# 18_Type_C.net
KiCad netlist of a schematic drawn in Altium Designer
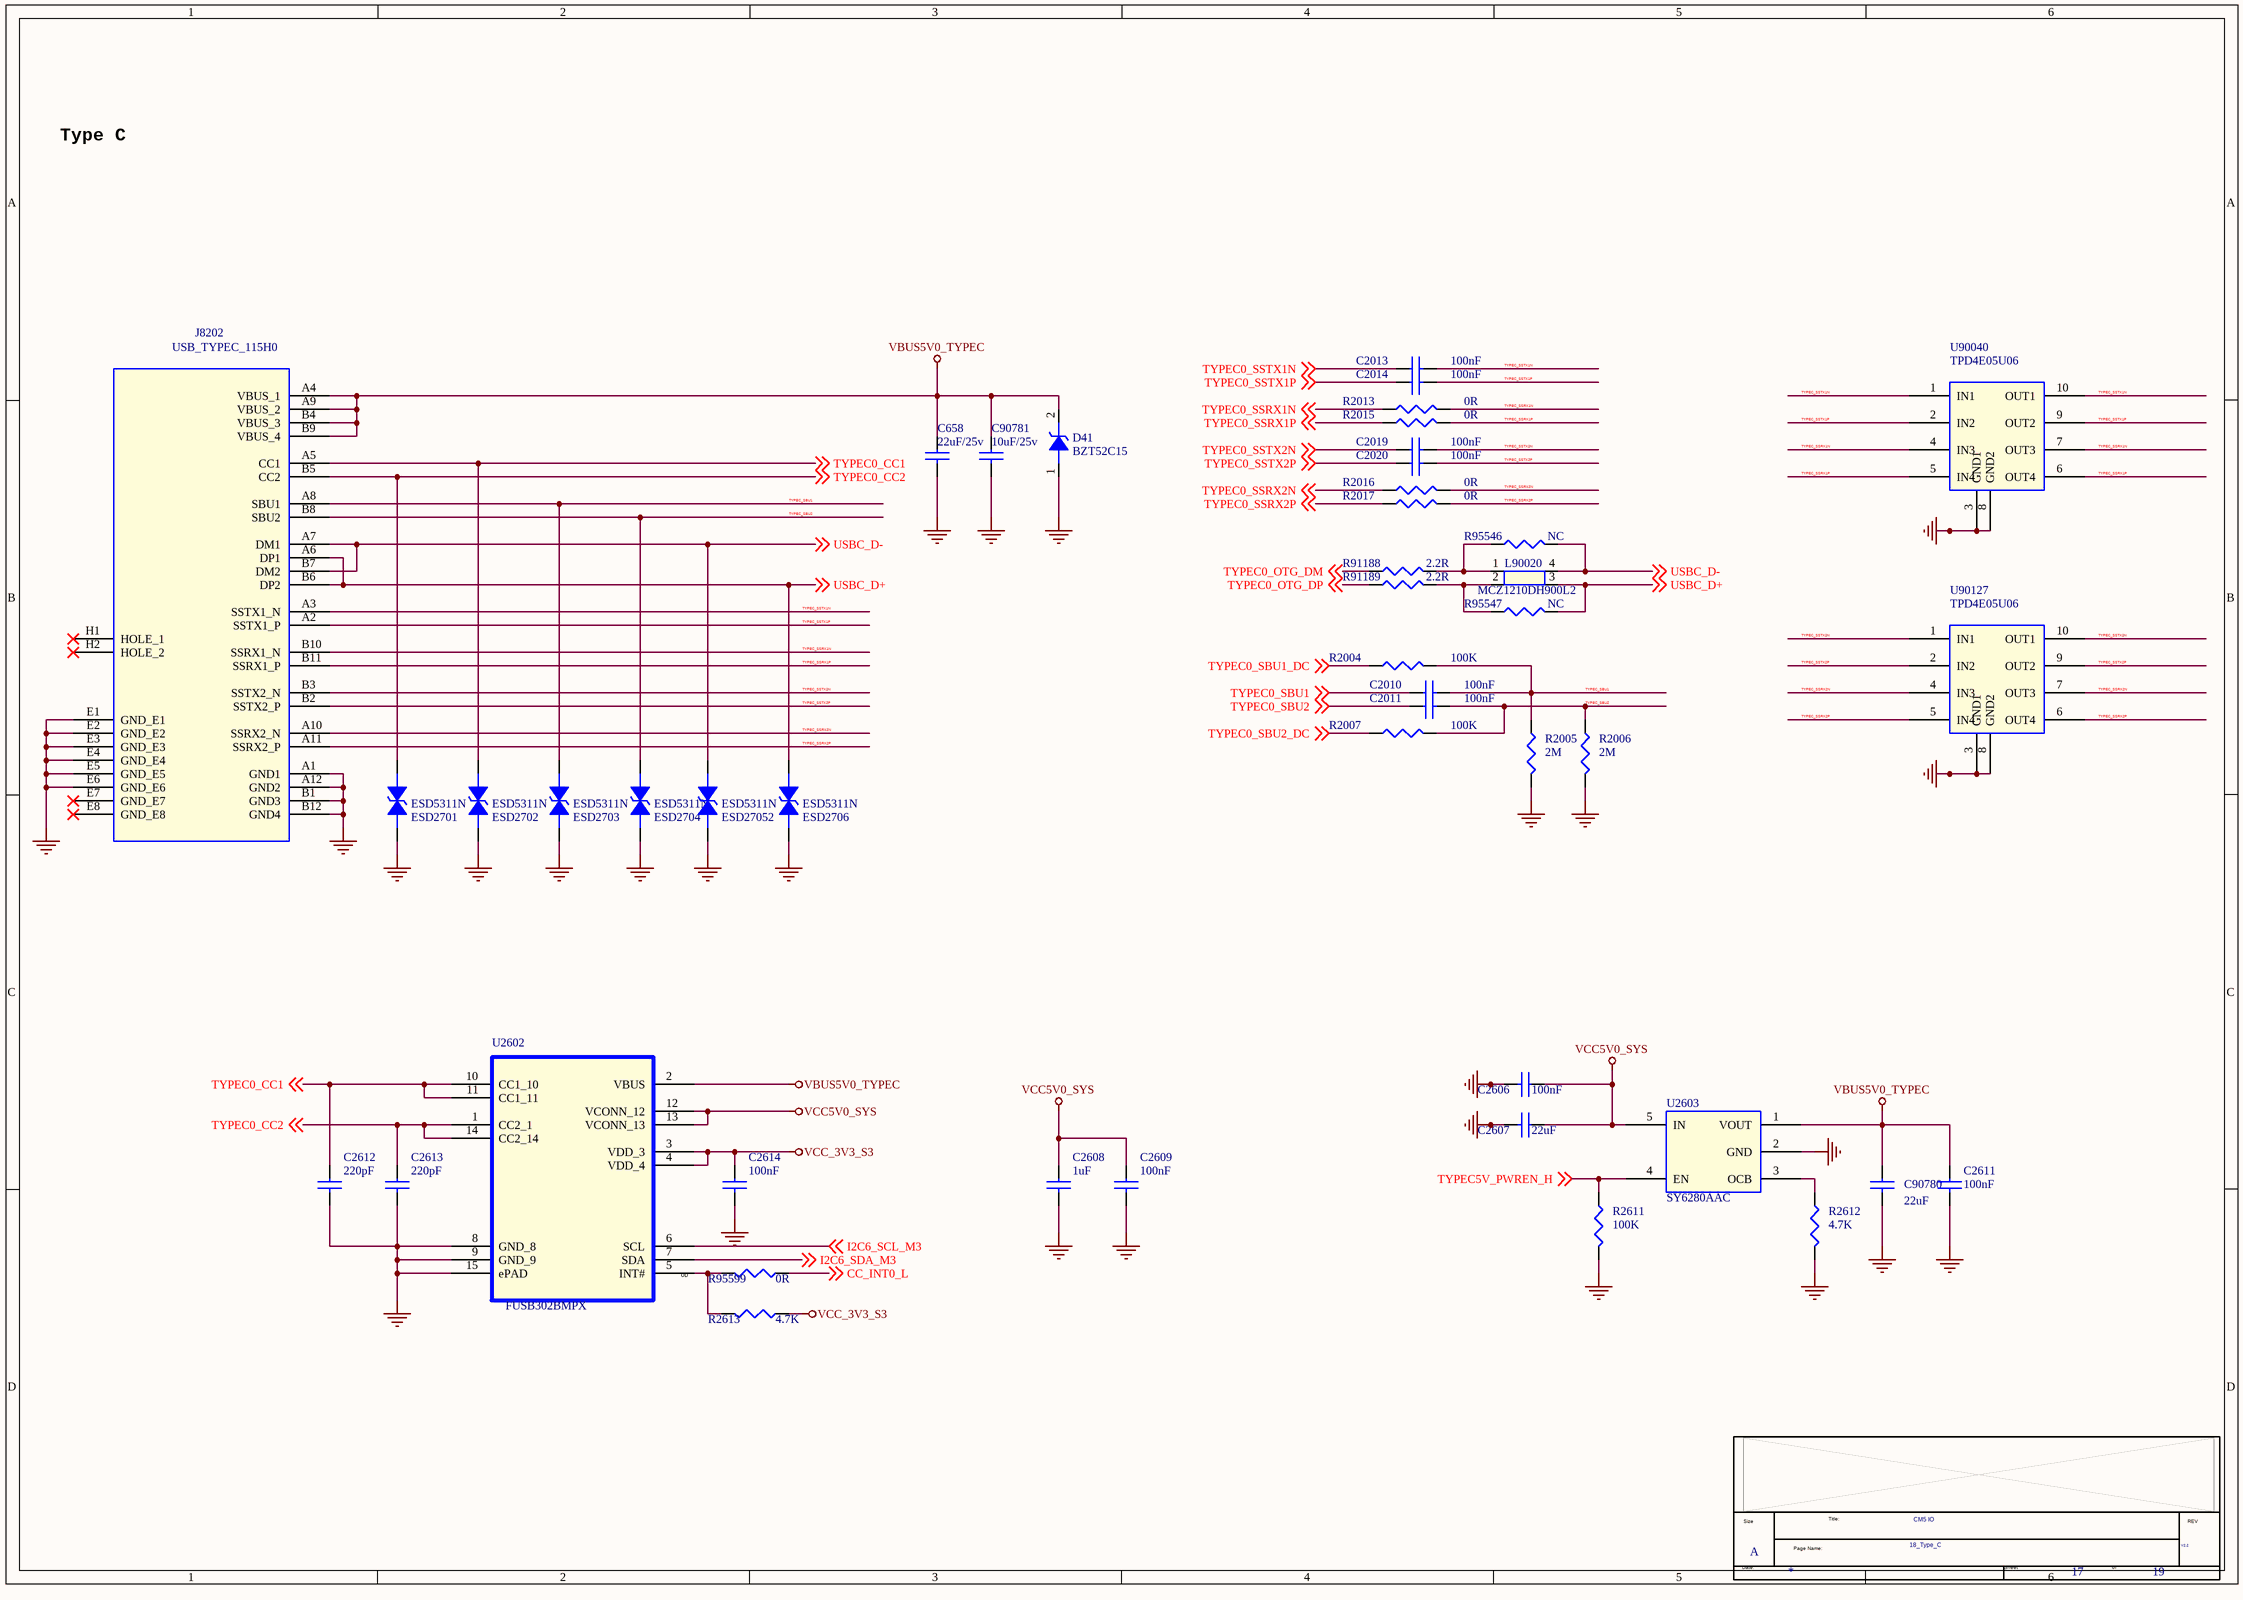
[diagram p0: 18_Type_C.SchDoc]

(export (version "E")
  (design (tool "Eeschema 10.0.6"))
  (components
    (comp (ref "*")
      (value "radxa_1010")
      (fields
        (field (name "DOC") "18_Type_C")
        (field (name "REVCODE") "V2.2")
        (field (name "TITLE") "CM5 IO")
        (field (name "PAGE SIZE") "A")
        (field (name "PAGE NUMBER") "17")
        (field (name "PAGE COUNT") "19")
      )
      (libsource (lib "*") (part "radxa_1010"))
    )
    (comp (ref "C658")
      (value "22uF/25v")
      (footprint "C0201")
      (description "0201 ∮ 10% 100nf X5R 6.3V")
      (libsource (lib "*") (part "C / 100 / nF / 0201_6"))
    )
    (comp (ref "C2010")
      (value "100nF")
      (footprint "C0201")
      (description "cap,100.00nF,+/-10%,10V,X5R,C0201")
      (fields
        (field (name "VOLTAGE") "10V")
        (field (name "TOLERANCE") "10%")
        (field (name "CREATED BY") "JJJ")
      )
      (libsource (lib "*") (part "CAP NP_0"))
    )
    (comp (ref "C2011")
      (value "100nF")
      (footprint "C0201")
      (description "cap,100.00nF,+/-10%,10V,X5R,C0201")
      (fields
        (field (name "VOLTAGE") "10V")
        (field (name "TOLERANCE") "10%")
        (field (name "CREATED BY") "JJJ")
      )
      (libsource (lib "*") (part "CAP NP_0"))
    )
    (comp (ref "C2013")
      (value "100nF")
      (footprint "C0201")
      (description "cap,100.00nF,+/-10%,10V,X5R,C0201")
      (fields
        (field (name "VOLTAGE") "10V")
        (field (name "TOLERANCE") "10%")
        (field (name "CREATED BY") "JJJ")
      )
      (libsource (lib "*") (part "CAP NP_0"))
    )
    (comp (ref "C2014")
      (value "100nF")
      (footprint "C0201")
      (description "cap,100.00nF,+/-10%,10V,X5R,C0201")
      (fields
        (field (name "VOLTAGE") "10V")
        (field (name "TOLERANCE") "10%")
        (field (name "CREATED BY") "JJJ")
      )
      (libsource (lib "*") (part "CAP NP_0"))
    )
    (comp (ref "C2019")
      (value "100nF")
      (footprint "C0201")
      (description "cap,100.00nF,+/-10%,10V,X5R,C0201")
      (fields
        (field (name "VOLTAGE") "10V")
        (field (name "TOLERANCE") "10%")
        (field (name "CREATED BY") "JJJ")
      )
      (libsource (lib "*") (part "CAP NP_0"))
    )
    (comp (ref "C2020")
      (value "100nF")
      (footprint "C0201")
      (description "cap,100.00nF,+/-10%,10V,X5R,C0201")
      (fields
        (field (name "VOLTAGE") "10V")
        (field (name "TOLERANCE") "10%")
        (field (name "CREATED BY") "JJJ")
      )
      (libsource (lib "*") (part "CAP NP_0"))
    )
    (comp (ref "C2606")
      (value "100nF")
      (footprint "C0402")
      (description "cap,100.00nF,+/-10%,16V,X5R,C0402")
      (fields
        (field (name "VOLTAGE") "16V")
        (field (name "MANUFACTURER") "TDK")
        (field (name "CREATED BY") "JJJ")
      )
      (libsource (lib "*") (part "CAP NP_0"))
    )
    (comp (ref "C2607")
      (value "22uF")
      (footprint "C0603")
      (description "cap,22.00uF,+/-20%,10V,X5R,C0603")
      (fields
        (field (name "VOLTAGE") "10V")
        (field (name "MANUFACTURER") "TDK")
        (field (name "CREATED BY") "JJJ")
      )
      (libsource (lib "*") (part "CAP NP_0"))
    )
    (comp (ref "C2608")
      (value "1uF")
      (footprint "C0402")
      (description "cap,1.00uF,+/-10%,16V,X5R,C0402")
      (fields
        (field (name "VOLTAGE") "16V")
        (field (name "TOLERANCE") "10%")
        (field (name "CREATED BY") "JJJ")
      )
      (libsource (lib "*") (part "CAP NP_0"))
    )
    (comp (ref "C2609")
      (value "100nF")
      (footprint "C0402")
      (description "cap,100.00nF,+/-10%,16V,X5R,C0402")
      (fields
        (field (name "VOLTAGE") "16V")
        (field (name "MANUFACTURER") "TDK")
        (field (name "CREATED BY") "JJJ")
      )
      (libsource (lib "*") (part "CAP NP_0"))
    )
    (comp (ref "C2611")
      (value "100nF")
      (footprint "C0402")
      (description "cap,100.00nF,+/-10%,16V,X5R,C0402")
      (fields
        (field (name "VOLTAGE") "25V")
        (field (name "TOLERANCE") "10%")
        (field (name "CREATED BY") "JJJ")
      )
      (libsource (lib "*") (part "CAP NP_0"))
    )
    (comp (ref "C2612")
      (value "220pF")
      (footprint "C0402")
      (description "cap,220.00pF,+/-5%,50V,C0G,C0402")
      (fields
        (field (name "VOLTAGE") "50V")
        (field (name "MANUFACTURER") "TDK")
        (field (name "CREATED BY") "JJJ")
      )
      (libsource (lib "*") (part "CAP NP_0"))
    )
    (comp (ref "C2613")
      (value "220pF")
      (footprint "C0402")
      (description "cap,220.00pF,+/-5%,50V,C0G,C0402")
      (fields
        (field (name "VOLTAGE") "50V")
        (field (name "TOLERANCE") "5%")
        (field (name "CREATED BY") "JJJ")
      )
      (libsource (lib "*") (part "CAP NP_0"))
    )
    (comp (ref "C2614")
      (value "100nF")
      (footprint "C0402")
      (description "cap,100.00nF,+/-10%,16V,X5R,C0402")
      (fields
        (field (name "VOLTAGE") "16V")
        (field (name "TOLERANCE") "10%")
        (field (name "CREATED BY") "JJJ")
      )
      (libsource (lib "*") (part "CAP NP_0"))
    )
    (comp (ref "C90780")
      (value "22uF")
      (footprint "C0805")
      (description "cap,22.00uF,+/-20%,10V,X5R,C0603")
      (fields
        (field (name "VOLTAGE") "25V")
        (field (name "TOLERANCE") "20%")
        (field (name "CREATED BY") "JJJ")
      )
      (libsource (lib "*") (part "CAP NP_0"))
    )
    (comp (ref "C90781")
      (value "10uF/25v")
      (footprint "C0201")
      (description "0201 ∮ 10% 100nf X5R 6.3V")
      (libsource (lib "*") (part "C / 100 / nF / 0201_6"))
    )
    (comp (ref "D41")
      (value "BZT52C15")
      (footprint "SOD_123")
      (description "ZENER DIODE,Vz=3.3V,BZT52C3V3,SOD-123")
      (fields (field (name "MANUFACTURER") "长电") (field (name "CREATED BY") "JJJ"))
      (libsource (lib "*") (part "DIODE ZENER1_0"))
    )
    (comp (ref "ESD2701")
      (value "ESD5311N")
      (footprint "ESD0402")
      (description "1-Line, Bi-directional, Transient Voltage Suppressors.1pF.")
      (fields (field (name "MANUFACTURER") "WillSemi(韦尔半导体)") (field (name "CREATED BY") "JJJ"))
      (libsource (lib "*") (part "DIODE BI_DIR TRIG_1_Dup1"))
    )
    (comp (ref "ESD2702")
      (value "ESD5311N")
      (footprint "ESD0402")
      (description "1-Line, Bi-directional, Transient Voltage Suppressors.1pF.")
      (fields (field (name "MANUFACTURER") "WillSemi(韦尔半导体)") (field (name "CREATED BY") "JJJ"))
      (libsource (lib "*") (part "DIODE BI_DIR TRIG_1_Dup1"))
    )
    (comp (ref "ESD2703")
      (value "ESD5311N")
      (footprint "ESD0402")
      (description "1-Line, Bi-directional, Transient Voltage Suppressors.1pF.")
      (fields (field (name "MANUFACTURER") "WillSemi(韦尔半导体)") (field (name "CREATED BY") "JJJ"))
      (libsource (lib "*") (part "DIODE BI_DIR TRIG_1_Dup1"))
    )
    (comp (ref "ESD2704")
      (value "ESD5311N")
      (footprint "ESD0402")
      (description "1-Line, Bi-directional, Transient Voltage Suppressors.1pF.")
      (fields (field (name "MANUFACTURER") "WillSemi(韦尔半导体)") (field (name "CREATED BY") "JJJ"))
      (libsource (lib "*") (part "DIODE BI_DIR TRIG_1_Dup1"))
    )
    (comp (ref "ESD2706")
      (value "ESD5311N")
      (footprint "ESD0402")
      (description "1-Line, Bi-directional, Transient Voltage Suppressors.1pF.")
      (fields (field (name "MANUFACTURER") "WillSemi(韦尔半导体)") (field (name "CREATED BY") "JJJ"))
      (libsource (lib "*") (part "DIODE BI_DIR TRIG_1_Dup1"))
    )
    (comp (ref "ESD27052")
      (value "ESD5311N")
      (footprint "ESD0402")
      (description "1-Line, Bi-directional, Transient Voltage Suppressors.1pF.")
      (fields (field (name "MANUFACTURER") "WillSemi(韦尔半导体)") (field (name "CREATED BY") "JJJ"))
      (libsource (lib "*") (part "DIODE BI_DIR TRIG_1_Dup1"))
    )
    (comp (ref "J8202")
      (value "USB_TYPEC_115H0")
      (footprint "TYPEC-24PIN-SMD-OK")
      (description "USB Type-C 连接座")
      (fields (field (name "MANUFACTURER") "泰科") (field (name "CREATED BY") "JJJ"))
      (libsource (lib "*") (part "USB31_TYPE_C"))
    )
    (comp (ref "L90020")
      (value "MCZ1210DH900L2")
      (footprint "MCZ1210AH900L2")
      (libsource (lib "*") (part "MCZ1210AH900L2_1_Dup1"))
    )
    (comp (ref "R2004")
      (value "100K")
      (footprint "R0402")
      (description "通用厚膜电阻,100K,+/-5%,R0201,1/20W.")
      (fields
        (field (name "TOLERANCE") "5%")
        (field (name "MANUFACTURER") "YAGEO")
        (field (name "CREATED BY") "YTL")
      )
      (libsource (lib "*") (part "RESISTOR_1"))
    )
    (comp (ref "R2005")
      (value "2M")
      (footprint "R0402")
      (description "通用厚膜电阻,2M,+/-5%,R0201,1/20W.")
      (fields
        (field (name "TOLERANCE") "5%")
        (field (name "MANUFACTURER") "YAGEO")
        (field (name "CREATED BY") "YTL")
      )
      (libsource (lib "*") (part "RESISTOR_1"))
    )
    (comp (ref "R2006")
      (value "2M")
      (footprint "R0402")
      (description "通用厚膜电阻,2M,+/-5%,R0201,1/20W.")
      (fields
        (field (name "TOLERANCE") "5%")
        (field (name "MANUFACTURER") "YAGEO")
        (field (name "CREATED BY") "YTL")
      )
      (libsource (lib "*") (part "RESISTOR_1"))
    )
    (comp (ref "R2007")
      (value "100K")
      (footprint "R0402")
      (description "通用厚膜电阻,100K,+/-5%,R0201,1/20W.")
      (fields
        (field (name "TOLERANCE") "5%")
        (field (name "MANUFACTURER") "YAGEO")
        (field (name "CREATED BY") "YTL")
      )
      (libsource (lib "*") (part "RESISTOR_1"))
    )
    (comp (ref "R2013")
      (value "0R")
      (footprint "R0402")
      (description "通用厚膜电阻,0R,+/-5%,R0201,1/20W.")
      (fields
        (field (name "TOLERANCE") "5%")
        (field (name "MANUFACTURER") "YAGEO")
        (field (name "CREATED BY") "YTL")
      )
      (libsource (lib "*") (part "RESISTOR_1"))
    )
    (comp (ref "R2015")
      (value "0R")
      (footprint "R0402")
      (description "通用厚膜电阻,0R,+/-5%,R0201,1/20W.")
      (fields
        (field (name "TOLERANCE") "5%")
        (field (name "MANUFACTURER") "YAGEO")
        (field (name "CREATED BY") "YTL")
      )
      (libsource (lib "*") (part "RESISTOR_1"))
    )
    (comp (ref "R2016")
      (value "0R")
      (footprint "R0402")
      (description "通用厚膜电阻,0R,+/-5%,R0201,1/20W.")
      (fields
        (field (name "TOLERANCE") "5%")
        (field (name "MANUFACTURER") "YAGEO")
        (field (name "CREATED BY") "YTL")
      )
      (libsource (lib "*") (part "RESISTOR_1"))
    )
    (comp (ref "R2017")
      (value "0R")
      (footprint "R0402")
      (description "通用厚膜电阻,0R,+/-5%,R0201,1/20W.")
      (fields
        (field (name "TOLERANCE") "5%")
        (field (name "MANUFACTURER") "YAGEO")
        (field (name "CREATED BY") "YTL")
      )
      (libsource (lib "*") (part "RESISTOR_1"))
    )
    (comp (ref "R2611")
      (value "100K")
      (footprint "R0402")
      (description "通用厚膜电阻,100K,+/-5%,R0402,1/16W.")
      (fields
        (field (name "TOLERANCE") "5%")
        (field (name "MANUFACTURER") "YAGEO")
        (field (name "CREATED BY") "YTL")
      )
      (libsource (lib "*") (part "RESISTOR_1"))
    )
    (comp (ref "R2612")
      (value "4.7K")
      (footprint "R0402")
      (description "通用厚膜电阻,4K7,+/-5%,R0402,1/16W.")
      (fields
        (field (name "TOLERANCE") "5%")
        (field (name "MANUFACTURER") "YAGEO")
        (field (name "CREATED BY") "YTL")
      )
      (libsource (lib "*") (part "RESISTOR_1"))
    )
    (comp (ref "R2613")
      (value "4.7K")
      (footprint "R0402")
      (description "通用厚膜电阻,10K,+/-5%,R0402,1/16W.")
      (fields
        (field (name "TOLERANCE") "5%")
        (field (name "MANUFACTURER") "YAGEO")
        (field (name "CREATED BY") "YTL")
      )
      (libsource (lib "*") (part "RESISTOR_1"))
    )
    (comp (ref "R91188")
      (value "2.2R")
      (footprint "R0402")
      (description "通用厚膜电阻,2R2,+/-5%,R0402,1/16W.")
      (fields
        (field (name "TOLERANCE") "5%")
        (field (name "MANUFACTURER") "YAGEO")
        (field (name "CREATED BY") "YTL")
      )
      (libsource (lib "*") (part "RESISTOR_0_Dup1"))
    )
    (comp (ref "R91189")
      (value "2.2R")
      (footprint "R0402")
      (description "通用厚膜电阻,2R2,+/-5%,R0402,1/16W.")
      (fields
        (field (name "TOLERANCE") "5%")
        (field (name "MANUFACTURER") "YAGEO")
        (field (name "CREATED BY") "YTL")
      )
      (libsource (lib "*") (part "RESISTOR_0_Dup1"))
    )
    (comp (ref "R95546")
      (value "NC")
      (footprint "R0402")
      (description "通用厚膜电阻,2R2,+/-5%,R0402,1/16W.")
      (fields
        (field (name "TOLERANCE") "5%")
        (field (name "MANUFACTURER") "YAGEO")
        (field (name "CREATED BY") "YTL")
      )
      (libsource (lib "*") (part "RESISTOR_0_Dup1"))
    )
    (comp (ref "R95547")
      (value "NC")
      (footprint "R0402")
      (description "通用厚膜电阻,2R2,+/-5%,R0402,1/16W.")
      (fields
        (field (name "TOLERANCE") "5%")
        (field (name "MANUFACTURER") "YAGEO")
        (field (name "CREATED BY") "YTL")
      )
      (libsource (lib "*") (part "RESISTOR_0_Dup1"))
    )
    (comp (ref "R95599")
      (value "0R")
      (footprint "R0402")
      (description "通用厚膜电阻,10K,+/-5%,R0402,1/16W.")
      (fields
        (field (name "TOLERANCE") "5%")
        (field (name "MANUFACTURER") "YAGEO")
        (field (name "CREATED BY") "YTL")
      )
      (libsource (lib "*") (part "RESISTOR_1"))
    )
    (comp (ref "U2602")
      (value "FUSB302BMPX")
      (footprint "MLP14_2R50X2R50X0R80")
      (description "Programmable USB Type-C Controller w/PD")
      (fields (field (name "MANUFACTURER") "Fairchild(飞兆半导体)") (field (name "CREATED BY") "JJJ"))
      (libsource (lib "*") (part "USB_FUSB302B"))
    )
    (comp (ref "U2603")
      (value "SY6280AAC")
      (footprint "SOT_23_5")
      (description "Low Loss Power Distribution Switch")
      (fields (field (name "MANUFACTURER") "Silergy（矽力杰）") (field (name "CREATED BY") "JJJ"))
      (libsource (lib "*") (part "SWITCH_SY6280"))
    )
    (comp (ref "U90040")
      (value "TPD4E05U06")
      (footprint "SON10_2R50X1R00X0R50")
      (description "unidirectional ESD protection devices with ultra low capacitance")
      (fields (field (name "MANUFACTURER") "TI（德州仪器）") (field (name "CREATED BY") "JJJ"))
      (libsource (lib "*") (part "ESD_TPD4E05U06"))
    )
    (comp (ref "U90127")
      (value "TPD4E05U06")
      (footprint "SON10_2R50X1R00X0R50")
      (description "unidirectional ESD protection devices with ultra low capacitance")
      (fields (field (name "MANUFACTURER") "TI（德州仪器）") (field (name "CREATED BY") "JJJ"))
      (libsource (lib "*") (part "ESD_TPD4E05U06"))
    )
  )
  (nets
    (net (code "1") (name "/TYPEC_SBU1") (class "Default")
      (node (ref "C2010") (pin "2") (pinfunction "2_2") (pintype "passive"))
      (node (ref "ESD2703") (pin "1") (pinfunction "1_1") (pintype "passive"))
      (node (ref "J8202") (pin "A8") (pinfunction "SBU1_A8") (pintype "passive"))
      (node (ref "R2004") (pin "2") (pinfunction "2_2") (pintype "passive"))
      (node (ref "R2005") (pin "1") (pinfunction "1_1") (pintype "passive"))
    )
    (net (code "2") (name "/TYPEC_SBU2") (class "Default")
      (node (ref "C2011") (pin "2") (pinfunction "2_2") (pintype "passive"))
      (node (ref "ESD2704") (pin "1") (pinfunction "1_1") (pintype "passive"))
      (node (ref "J8202") (pin "B8") (pinfunction "SBU2_B8") (pintype "passive"))
      (node (ref "R2006") (pin "1") (pinfunction "1_1") (pintype "passive"))
      (node (ref "R2007") (pin "2") (pinfunction "2_2") (pintype "passive"))
    )
    (net (code "3") (name "/TYPEC_SSRX1N") (class "Default")
      (node (ref "J8202") (pin "B10") (pinfunction "SSRX1_N_B10") (pintype "passive"))
      (node (ref "R2013") (pin "2") (pinfunction "2_2") (pintype "passive"))
      (node (ref "U90040") (pin "4") (pinfunction "IN3_4") (pintype "passive"))
      (node (ref "U90040") (pin "7") (pinfunction "OUT3_7") (pintype "passive"))
    )
    (net (code "4") (name "/TYPEC_SSRX1P") (class "Default")
      (node (ref "J8202") (pin "B11") (pinfunction "SSRX1_P_B11") (pintype "passive"))
      (node (ref "R2015") (pin "2") (pinfunction "2_2") (pintype "passive"))
      (node (ref "U90040") (pin "5") (pinfunction "IN4_5") (pintype "passive"))
      (node (ref "U90040") (pin "6") (pinfunction "OUT4_6") (pintype "passive"))
    )
    (net (code "5") (name "/TYPEC_SSRX2N") (class "Default")
      (node (ref "J8202") (pin "A10") (pinfunction "SSRX2_N_A10") (pintype "passive"))
      (node (ref "R2016") (pin "2") (pinfunction "2_2") (pintype "passive"))
      (node (ref "U90127") (pin "4") (pinfunction "IN3_4") (pintype "passive"))
      (node (ref "U90127") (pin "7") (pinfunction "OUT3_7") (pintype "passive"))
    )
    (net (code "6") (name "/TYPEC_SSRX2P") (class "Default")
      (node (ref "J8202") (pin "A11") (pinfunction "SSRX2_P_A11") (pintype "passive"))
      (node (ref "R2017") (pin "2") (pinfunction "2_2") (pintype "passive"))
      (node (ref "U90127") (pin "5") (pinfunction "IN4_5") (pintype "passive"))
      (node (ref "U90127") (pin "6") (pinfunction "OUT4_6") (pintype "passive"))
    )
    (net (code "7") (name "/TYPEC_SSTX1N") (class "Default")
      (node (ref "C2013") (pin "2") (pinfunction "2_2") (pintype "passive"))
      (node (ref "J8202") (pin "A3") (pinfunction "SSTX1_N_A3") (pintype "passive"))
      (node (ref "U90040") (pin "1") (pinfunction "IN1_1") (pintype "passive"))
      (node (ref "U90040") (pin "10") (pinfunction "OUT1_10") (pintype "passive"))
    )
    (net (code "8") (name "/TYPEC_SSTX1P") (class "Default")
      (node (ref "C2014") (pin "2") (pinfunction "2_2") (pintype "passive"))
      (node (ref "J8202") (pin "A2") (pinfunction "SSTX1_P_A2") (pintype "passive"))
      (node (ref "U90040") (pin "2") (pinfunction "IN2_2") (pintype "passive"))
      (node (ref "U90040") (pin "9") (pinfunction "OUT2_9") (pintype "passive"))
    )
    (net (code "9") (name "/TYPEC_SSTX2N") (class "Default")
      (node (ref "C2019") (pin "2") (pinfunction "2_2") (pintype "passive"))
      (node (ref "J8202") (pin "B3") (pinfunction "SSTX2_N_B3") (pintype "passive"))
      (node (ref "U90127") (pin "1") (pinfunction "IN1_1") (pintype "passive"))
      (node (ref "U90127") (pin "10") (pinfunction "OUT1_10") (pintype "passive"))
    )
    (net (code "10") (name "/TYPEC_SSTX2P") (class "Default")
      (node (ref "C2020") (pin "2") (pinfunction "2_2") (pintype "passive"))
      (node (ref "J8202") (pin "B2") (pinfunction "SSTX2_P_B2") (pintype "passive"))
      (node (ref "U90127") (pin "2") (pinfunction "IN2_2") (pintype "passive"))
      (node (ref "U90127") (pin "9") (pinfunction "OUT2_9") (pintype "passive"))
    )
    (net (code "11") (name "CC_INT0_L") (class "Default")
      (node (ref "R95599") (pin "1") (pinfunction "1_1") (pintype "passive"))
    )
    (net (code "12") (name "GND") (class "Default")
      (node (ref "C2606") (pin "2") (pinfunction "2_2") (pintype "passive"))
      (node (ref "C2607") (pin "2") (pinfunction "2_2") (pintype "passive"))
      (node (ref "C2608") (pin "2") (pinfunction "2_2") (pintype "passive"))
      (node (ref "C2609") (pin "2") (pinfunction "2_2") (pintype "passive"))
      (node (ref "C2611") (pin "2") (pinfunction "2_2") (pintype "passive"))
      (node (ref "C2612") (pin "2") (pinfunction "2_2") (pintype "passive"))
      (node (ref "C2613") (pin "2") (pinfunction "2_2") (pintype "passive"))
      (node (ref "C2614") (pin "2") (pinfunction "2_2") (pintype "passive"))
      (node (ref "C658") (pin "2") (pinfunction "2_2") (pintype "passive"))
      (node (ref "C90780") (pin "2") (pinfunction "2_2") (pintype "passive"))
      (node (ref "C90781") (pin "2") (pinfunction "2_2") (pintype "passive"))
      (node (ref "D41") (pin "1") (pinfunction "ANODE_1") (pintype "passive"))
      (node (ref "ESD2701") (pin "2") (pinfunction "2_2") (pintype "passive"))
      (node (ref "ESD2702") (pin "2") (pinfunction "2_2") (pintype "passive"))
      (node (ref "ESD2703") (pin "2") (pinfunction "2_2") (pintype "passive"))
      (node (ref "ESD2704") (pin "2") (pinfunction "2_2") (pintype "passive"))
      (node (ref "ESD27052") (pin "2") (pinfunction "2_2") (pintype "passive"))
      (node (ref "ESD2706") (pin "2") (pinfunction "2_2") (pintype "passive"))
      (node (ref "J8202") (pin "A1") (pinfunction "GND1_A1") (pintype "passive"))
      (node (ref "J8202") (pin "A12") (pinfunction "GND2_A12") (pintype "passive"))
      (node (ref "J8202") (pin "B1") (pinfunction "GND3_B1") (pintype "passive"))
      (node (ref "J8202") (pin "B12") (pinfunction "GND4_B12") (pintype "passive"))
      (node (ref "J8202") (pin "E1") (pinfunction "GND_E1_E1") (pintype "passive"))
      (node (ref "J8202") (pin "E2") (pinfunction "GND_E2_E2") (pintype "passive"))
      (node (ref "J8202") (pin "E3") (pinfunction "GND_E3_E3") (pintype "passive"))
      (node (ref "J8202") (pin "E4") (pinfunction "GND_E4_E4") (pintype "passive"))
      (node (ref "J8202") (pin "E5") (pinfunction "GND_E5_E5") (pintype "passive"))
      (node (ref "J8202") (pin "E6") (pinfunction "GND_E6_E6") (pintype "passive"))
      (node (ref "R2005") (pin "2") (pinfunction "2_2") (pintype "passive"))
      (node (ref "R2006") (pin "2") (pinfunction "2_2") (pintype "passive"))
      (node (ref "R2611") (pin "2") (pinfunction "2_2") (pintype "passive"))
      (node (ref "R2612") (pin "2") (pinfunction "2_2") (pintype "passive"))
      (node (ref "U2602") (pin "15") (pinfunction "ePAD_15") (pintype "power_in"))
      (node (ref "U2602") (pin "8") (pinfunction "GND_8_8") (pintype "power_in"))
      (node (ref "U2602") (pin "9") (pinfunction "GND_9_9") (pintype "power_in"))
      (node (ref "U2603") (pin "2") (pinfunction "GND_2") (pintype "passive"))
      (node (ref "U90040") (pin "3") (pinfunction "GND1_3") (pintype "passive"))
      (node (ref "U90040") (pin "8") (pinfunction "GND2_8") (pintype "passive"))
      (node (ref "U90127") (pin "3") (pinfunction "GND1_3") (pintype "passive"))
      (node (ref "U90127") (pin "8") (pinfunction "GND2_8") (pintype "passive"))
    )
    (net (code "13") (name "I2C6_SCL_M3") (class "Default")
      (node (ref "U2602") (pin "6") (pinfunction "SCL_6") (pintype "passive"))
    )
    (net (code "14") (name "I2C6_SDA_M3") (class "Default")
      (node (ref "U2602") (pin "7") (pinfunction "SDA_7") (pintype "passive"))
    )
    (net (code "15") (name "Net-(L90020-Pad1)") (class "Default")
      (node (ref "L90020") (pin "1") (pinfunction "1_1") (pintype "passive"))
      (node (ref "R91188") (pin "2") (pinfunction "2_2") (pintype "passive"))
      (node (ref "R95546") (pin "1") (pinfunction "1_1") (pintype "passive"))
    )
    (net (code "16") (name "Net-(L90020-Pad2)") (class "Default")
      (node (ref "L90020") (pin "2") (pinfunction "2_2") (pintype "passive"))
      (node (ref "R91189") (pin "2") (pinfunction "2_2") (pintype "passive"))
      (node (ref "R95547") (pin "1") (pinfunction "1_1") (pintype "passive"))
    )
    (net (code "17") (name "Net-(U2602-INT#)") (class "Default")
      (node (ref "R2613") (pin "2") (pinfunction "2_2") (pintype "passive"))
      (node (ref "R95599") (pin "2") (pinfunction "2_2") (pintype "passive"))
      (node (ref "U2602") (pin "5") (pinfunction "INT#_5") (pintype "passive"))
    )
    (net (code "18") (name "Net-(U2603-OCB)") (class "Default")
      (node (ref "R2612") (pin "1") (pinfunction "1_1") (pintype "passive"))
      (node (ref "U2603") (pin "3") (pinfunction "OCB_3") (pintype "passive"))
    )
    (net (code "19") (name "TYPEC0_CC1") (class "Default")
      (node (ref "C2612") (pin "1") (pinfunction "1_1") (pintype "passive"))
      (node (ref "ESD2702") (pin "1") (pinfunction "1_1") (pintype "passive"))
      (node (ref "J8202") (pin "A5") (pinfunction "CC1_A5") (pintype "passive"))
      (node (ref "U2602") (pin "10") (pinfunction "CC1_10_10") (pintype "passive"))
      (node (ref "U2602") (pin "11") (pinfunction "CC1_11_11") (pintype "passive"))
    )
    (net (code "20") (name "TYPEC0_CC2") (class "Default")
      (node (ref "C2613") (pin "1") (pinfunction "1_1") (pintype "passive"))
      (node (ref "ESD2701") (pin "1") (pinfunction "1_1") (pintype "passive"))
      (node (ref "J8202") (pin "B5") (pinfunction "CC2_B5") (pintype "passive"))
      (node (ref "U2602") (pin "1") (pinfunction "CC2_1_1") (pintype "passive"))
      (node (ref "U2602") (pin "14") (pinfunction "CC2_14_14") (pintype "passive"))
    )
    (net (code "21") (name "TYPEC0_OTG_DM") (class "Default")
      (node (ref "R91188") (pin "1") (pinfunction "1_1") (pintype "passive"))
    )
    (net (code "22") (name "TYPEC0_OTG_DP") (class "Default")
      (node (ref "R91189") (pin "1") (pinfunction "1_1") (pintype "passive"))
    )
    (net (code "23") (name "TYPEC0_SBU1") (class "Default")
      (node (ref "C2010") (pin "1") (pinfunction "1_1") (pintype "passive"))
    )
    (net (code "24") (name "TYPEC0_SBU1_DC") (class "Default")
      (node (ref "R2004") (pin "1") (pinfunction "1_1") (pintype "passive"))
    )
    (net (code "25") (name "TYPEC0_SBU2") (class "Default")
      (node (ref "C2011") (pin "1") (pinfunction "1_1") (pintype "passive"))
    )
    (net (code "26") (name "TYPEC0_SBU2_DC") (class "Default")
      (node (ref "R2007") (pin "1") (pinfunction "1_1") (pintype "passive"))
    )
    (net (code "27") (name "TYPEC0_SSRX1N") (class "Default")
      (node (ref "R2013") (pin "1") (pinfunction "1_1") (pintype "passive"))
    )
    (net (code "28") (name "TYPEC0_SSRX1P") (class "Default")
      (node (ref "R2015") (pin "1") (pinfunction "1_1") (pintype "passive"))
    )
    (net (code "29") (name "TYPEC0_SSRX2N") (class "Default")
      (node (ref "R2016") (pin "1") (pinfunction "1_1") (pintype "passive"))
    )
    (net (code "30") (name "TYPEC0_SSRX2P") (class "Default")
      (node (ref "R2017") (pin "1") (pinfunction "1_1") (pintype "passive"))
    )
    (net (code "31") (name "TYPEC0_SSTX1N") (class "Default")
      (node (ref "C2013") (pin "1") (pinfunction "1_1") (pintype "passive"))
    )
    (net (code "32") (name "TYPEC0_SSTX1P") (class "Default")
      (node (ref "C2014") (pin "1") (pinfunction "1_1") (pintype "passive"))
    )
    (net (code "33") (name "TYPEC0_SSTX2N") (class "Default")
      (node (ref "C2019") (pin "1") (pinfunction "1_1") (pintype "passive"))
    )
    (net (code "34") (name "TYPEC0_SSTX2P") (class "Default")
      (node (ref "C2020") (pin "1") (pinfunction "1_1") (pintype "passive"))
    )
    (net (code "35") (name "TYPEC5V_PWREN_H") (class "Default")
      (node (ref "R2611") (pin "1") (pinfunction "1_1") (pintype "passive"))
      (node (ref "U2603") (pin "4") (pinfunction "EN_4") (pintype "passive"))
    )
    (net (code "36") (name "USBC_D+") (class "Default")
      (node (ref "ESD2706") (pin "1") (pinfunction "1_1") (pintype "passive"))
      (node (ref "J8202") (pin "A6") (pinfunction "DP1_A6") (pintype "passive"))
      (node (ref "J8202") (pin "B6") (pinfunction "DP2_B6") (pintype "passive"))
      (node (ref "L90020") (pin "3") (pinfunction "3_3") (pintype "passive"))
      (node (ref "R95547") (pin "2") (pinfunction "2_2") (pintype "passive"))
    )
    (net (code "37") (name "USBC_D-") (class "Default")
      (node (ref "ESD27052") (pin "1") (pinfunction "1_1") (pintype "passive"))
      (node (ref "J8202") (pin "A7") (pinfunction "DM1_A7") (pintype "passive"))
      (node (ref "J8202") (pin "B7") (pinfunction "DM2_B7") (pintype "passive"))
      (node (ref "L90020") (pin "4") (pinfunction "4_4") (pintype "passive"))
      (node (ref "R95546") (pin "2") (pinfunction "2_2") (pintype "passive"))
    )
    (net (code "38") (name "VBUS5V0_TYPEC") (class "Default")
      (node (ref "C2611") (pin "1") (pinfunction "1_1") (pintype "passive"))
      (node (ref "C658") (pin "1") (pinfunction "1_1") (pintype "passive"))
      (node (ref "C90780") (pin "1") (pinfunction "1_1") (pintype "passive"))
      (node (ref "C90781") (pin "1") (pinfunction "1_1") (pintype "passive"))
      (node (ref "D41") (pin "2") (pinfunction "CATHODE_2") (pintype "passive"))
      (node (ref "J8202") (pin "A4") (pinfunction "VBUS_1_A4") (pintype "passive"))
      (node (ref "J8202") (pin "A9") (pinfunction "VBUS_2_A9") (pintype "passive"))
      (node (ref "J8202") (pin "B4") (pinfunction "VBUS_3_B4") (pintype "passive"))
      (node (ref "J8202") (pin "B9") (pinfunction "VBUS_4_B9") (pintype "passive"))
      (node (ref "U2602") (pin "2") (pinfunction "VBUS_2") (pintype "passive"))
      (node (ref "U2603") (pin "1") (pinfunction "VOUT_1") (pintype "passive"))
    )
    (net (code "39") (name "VCC5V0_SYS") (class "Default")
      (node (ref "C2606") (pin "1") (pinfunction "1_1") (pintype "passive"))
      (node (ref "C2607") (pin "1") (pinfunction "1_1") (pintype "passive"))
      (node (ref "C2608") (pin "1") (pinfunction "1_1") (pintype "passive"))
      (node (ref "C2609") (pin "1") (pinfunction "1_1") (pintype "passive"))
      (node (ref "U2602") (pin "12") (pinfunction "VCONN_12_12") (pintype "passive"))
      (node (ref "U2602") (pin "13") (pinfunction "VCONN_13_13") (pintype "passive"))
      (node (ref "U2603") (pin "5") (pinfunction "IN_5") (pintype "passive"))
    )
    (net (code "40") (name "VCC_3V3_S3") (class "Default")
      (node (ref "C2614") (pin "1") (pinfunction "1_1") (pintype "passive"))
      (node (ref "R2613") (pin "1") (pinfunction "1_1") (pintype "passive"))
      (node (ref "U2602") (pin "3") (pinfunction "VDD_3_3") (pintype "power_in"))
      (node (ref "U2602") (pin "4") (pinfunction "VDD_4_4") (pintype "power_in"))
    )
    (net (code "41") (name "unconnected-(J8202-GND_E7-PadE7)") (class "Default")
      (node (ref "J8202") (pin "E7") (pinfunction "GND_E7_E7") (pintype "passive+no_connect"))
    )
    (net (code "42") (name "unconnected-(J8202-GND_E8-PadE8)") (class "Default")
      (node (ref "J8202") (pin "E8") (pinfunction "GND_E8_E8") (pintype "passive+no_connect"))
    )
    (net (code "43") (name "unconnected-(J8202-HOLE_1-PadH1)") (class "Default")
      (node (ref "J8202") (pin "H1") (pinfunction "HOLE_1_H1") (pintype "passive+no_connect"))
    )
    (net (code "44") (name "unconnected-(J8202-HOLE_2-PadH2)") (class "Default")
      (node (ref "J8202") (pin "H2") (pinfunction "HOLE_2_H2") (pintype "passive+no_connect"))
    )
  )
)
